# design.net
KiCad netlist of a schematic drawn in EasyEDA Pro
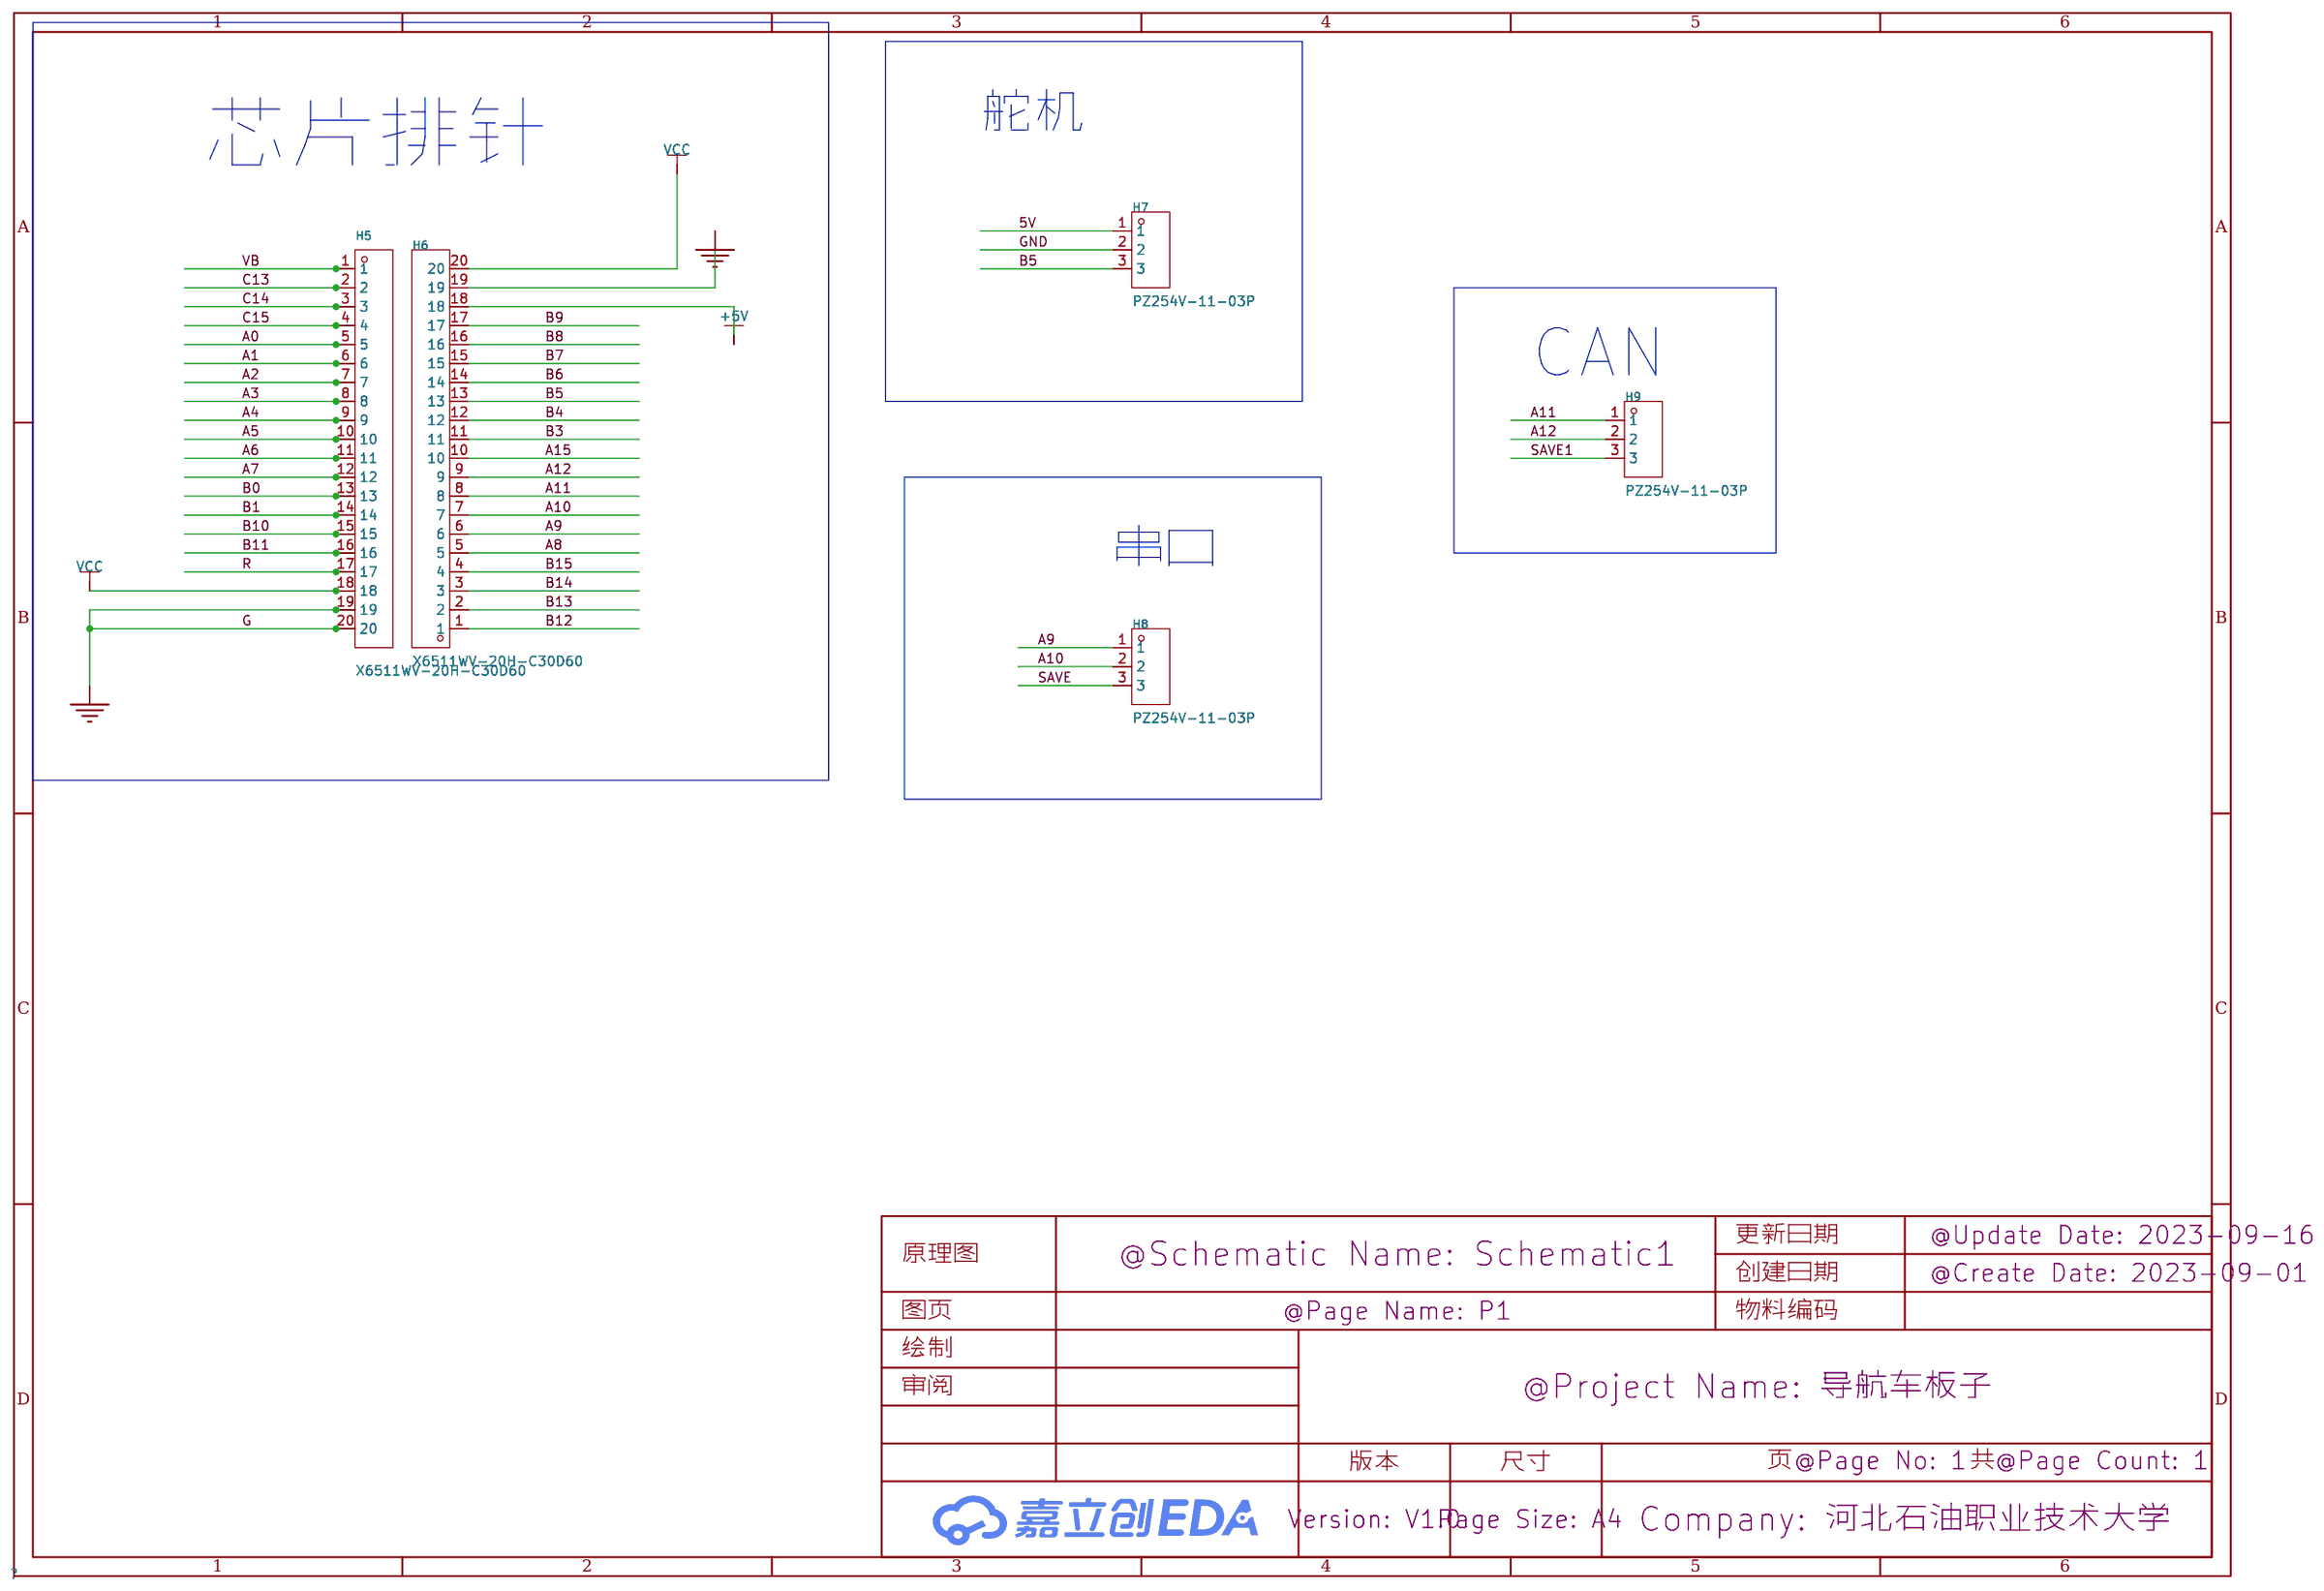
[diagram p0: schematic sheet]

(export (version "E")
  (design (tool "Eeschema 10.0.6"))
  (components
    (comp (ref "H5")
      (value "X6511WV-20H-C30D60")
      (footprint "easyedapro:HDR-TH_20P-P2.54-V-M")
      (fields (field (name "Manufacturer") "XKB Connectivity(中国星坤)"))
      (libsource (lib "easyedapro") (part "X6511WV-20H-C30D60"))
    )
    (comp (ref "H6")
      (value "X6511WV-20H-C30D60")
      (footprint "easyedapro:HDR-TH_20P-P2.54-V-M")
      (fields (field (name "Manufacturer") "XKB Connectivity(中国星坤)"))
      (libsource (lib "easyedapro") (part "X6511WV-20H-C30D60"))
    )
    (comp (ref "H7")
      (value "PZ254V-11-03P")
      (footprint "easyedapro:HDR-TH_3P-P2.54-V-M")
      (fields (field (name "Manufacturer") "XFCN(兴飞)"))
      (libsource (lib "easyedapro") (part "PZ254V-11-03P_C2937625"))
    )
    (comp (ref "H8")
      (value "PZ254V-11-03P")
      (footprint "easyedapro:HDR-TH_3P-P2.54-V-M")
      (fields (field (name "Manufacturer") "XFCN(兴飞)"))
      (libsource (lib "easyedapro") (part "PZ254V-11-03P_C2937625"))
    )
    (comp (ref "H9")
      (value "PZ254V-11-03P")
      (footprint "easyedapro:HDR-TH_3P-P2.54-V-M")
      (fields (field (name "Manufacturer") "XFCN(兴飞)"))
      (libsource (lib "easyedapro") (part "PZ254V-11-03P_C2937625"))
    )
  )
  (nets
    (net (code "1") (name "+5V") (class "Default")
      (node (ref "H6") (pin "18") (pinfunction "18_18") (pintype "input"))
    )
    (net (code "2") (name "/5V") (class "Default")
      (node (ref "H7") (pin "1") (pinfunction "1_1") (pintype "input"))
    )
    (net (code "3") (name "/A0") (class "Default")
      (node (ref "H5") (pin "5") (pinfunction "5_5") (pintype "input"))
    )
    (net (code "4") (name "/A1") (class "Default")
      (node (ref "H5") (pin "6") (pinfunction "6_6") (pintype "input"))
    )
    (net (code "5") (name "/A2") (class "Default")
      (node (ref "H5") (pin "7") (pinfunction "7_7") (pintype "input"))
    )
    (net (code "6") (name "/A3") (class "Default")
      (node (ref "H5") (pin "8") (pinfunction "8_8") (pintype "input"))
    )
    (net (code "7") (name "/A4") (class "Default")
      (node (ref "H5") (pin "9") (pinfunction "9_9") (pintype "input"))
    )
    (net (code "8") (name "/A5") (class "Default")
      (node (ref "H5") (pin "10") (pinfunction "10_10") (pintype "input"))
    )
    (net (code "9") (name "/A6") (class "Default")
      (node (ref "H5") (pin "11") (pinfunction "11_11") (pintype "input"))
    )
    (net (code "10") (name "/A7") (class "Default")
      (node (ref "H5") (pin "12") (pinfunction "12_12") (pintype "input"))
    )
    (net (code "11") (name "/A8") (class "Default")
      (node (ref "H6") (pin "5") (pinfunction "5_5") (pintype "input"))
    )
    (net (code "12") (name "/A9") (class "Default")
      (node (ref "H6") (pin "6") (pinfunction "6_6") (pintype "input"))
      (node (ref "H8") (pin "1") (pinfunction "1_1") (pintype "input"))
    )
    (net (code "13") (name "/A10") (class "Default")
      (node (ref "H6") (pin "7") (pinfunction "7_7") (pintype "input"))
      (node (ref "H8") (pin "2") (pinfunction "2_2") (pintype "input"))
    )
    (net (code "14") (name "/A11") (class "Default")
      (node (ref "H6") (pin "8") (pinfunction "8_8") (pintype "input"))
      (node (ref "H9") (pin "1") (pinfunction "1_1") (pintype "input"))
    )
    (net (code "15") (name "/A12") (class "Default")
      (node (ref "H6") (pin "9") (pinfunction "9_9") (pintype "input"))
      (node (ref "H9") (pin "2") (pinfunction "2_2") (pintype "input"))
    )
    (net (code "16") (name "/A15") (class "Default")
      (node (ref "H6") (pin "10") (pinfunction "10_10") (pintype "input"))
    )
    (net (code "17") (name "/B0") (class "Default")
      (node (ref "H5") (pin "13") (pinfunction "13_13") (pintype "input"))
    )
    (net (code "18") (name "/B1") (class "Default")
      (node (ref "H5") (pin "14") (pinfunction "14_14") (pintype "input"))
    )
    (net (code "19") (name "/B3") (class "Default")
      (node (ref "H6") (pin "11") (pinfunction "11_11") (pintype "input"))
    )
    (net (code "20") (name "/B4") (class "Default")
      (node (ref "H6") (pin "12") (pinfunction "12_12") (pintype "input"))
    )
    (net (code "21") (name "/B5") (class "Default")
      (node (ref "H6") (pin "13") (pinfunction "13_13") (pintype "input"))
      (node (ref "H7") (pin "3") (pinfunction "3_3") (pintype "input"))
    )
    (net (code "22") (name "/B6") (class "Default")
      (node (ref "H6") (pin "14") (pinfunction "14_14") (pintype "input"))
    )
    (net (code "23") (name "/B7") (class "Default")
      (node (ref "H6") (pin "15") (pinfunction "15_15") (pintype "input"))
    )
    (net (code "24") (name "/B8") (class "Default")
      (node (ref "H6") (pin "16") (pinfunction "16_16") (pintype "input"))
    )
    (net (code "25") (name "/B9") (class "Default")
      (node (ref "H6") (pin "17") (pinfunction "17_17") (pintype "input"))
    )
    (net (code "26") (name "/B10") (class "Default")
      (node (ref "H5") (pin "15") (pinfunction "15_15") (pintype "input"))
    )
    (net (code "27") (name "/B11") (class "Default")
      (node (ref "H5") (pin "16") (pinfunction "16_16") (pintype "input"))
    )
    (net (code "28") (name "/B12") (class "Default")
      (node (ref "H6") (pin "1") (pinfunction "1_1") (pintype "input"))
    )
    (net (code "29") (name "/B13") (class "Default")
      (node (ref "H6") (pin "2") (pinfunction "2_2") (pintype "input"))
    )
    (net (code "30") (name "/B14") (class "Default")
      (node (ref "H6") (pin "3") (pinfunction "3_3") (pintype "input"))
    )
    (net (code "31") (name "/B15") (class "Default")
      (node (ref "H6") (pin "4") (pinfunction "4_4") (pintype "input"))
    )
    (net (code "32") (name "/C13") (class "Default")
      (node (ref "H5") (pin "2") (pinfunction "2_2") (pintype "input"))
    )
    (net (code "33") (name "/C14") (class "Default")
      (node (ref "H5") (pin "3") (pinfunction "3_3") (pintype "input"))
    )
    (net (code "34") (name "/C15") (class "Default")
      (node (ref "H5") (pin "4") (pinfunction "4_4") (pintype "input"))
    )
    (net (code "35") (name "/R") (class "Default")
      (node (ref "H5") (pin "17") (pinfunction "17_17") (pintype "input"))
    )
    (net (code "36") (name "/SAVE") (class "Default")
      (node (ref "H8") (pin "3") (pinfunction "3_3") (pintype "input"))
    )
    (net (code "37") (name "/SAVE1") (class "Default")
      (node (ref "H9") (pin "3") (pinfunction "3_3") (pintype "input"))
    )
    (net (code "38") (name "/VB") (class "Default")
      (node (ref "H5") (pin "1") (pinfunction "1_1") (pintype "input"))
    )
    (net (code "39") (name "G") (class "Default")
      (node (ref "H5") (pin "19") (pinfunction "19_19") (pintype "input"))
      (node (ref "H5") (pin "20") (pinfunction "20_20") (pintype "input"))
    )
    (net (code "40") (name "GND") (class "Default")
      (node (ref "H6") (pin "19") (pinfunction "19_19") (pintype "input"))
      (node (ref "H7") (pin "2") (pinfunction "2_2") (pintype "input"))
    )
    (net (code "41") (name "VCC") (class "Default")
      (node (ref "H5") (pin "18") (pinfunction "18_18") (pintype "input"))
      (node (ref "H6") (pin "20") (pinfunction "20_20") (pintype "input"))
    )
  )
)
